# kill-switches_schematic.net
KiCad netlist of a schematic drawn in Altium Designer
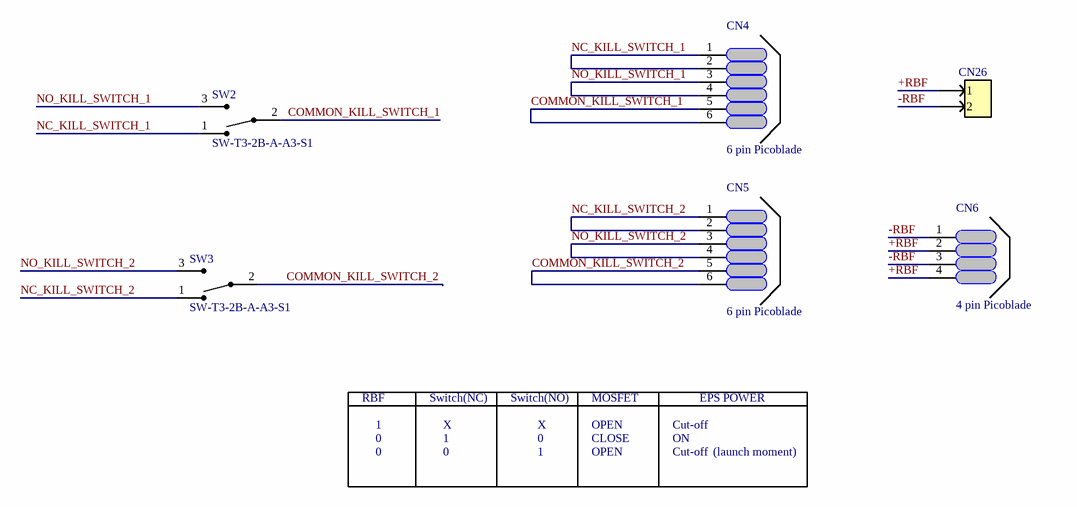
[diagram p0: kill-switches_schematic.SchDoc]

(export (version "E")
  (design (tool "Eeschema 10.0.6"))
  (components
    (comp (ref "CN4")
      (value "6 pin Picoblade")
      (footprint "PICO BLADE 0532610671")
      (description "1.25mm Pitch PicoBlade™ Header, Surface Mount, Vertical, 6 Circuits")
      (fields (field (name "MANUFACTURER") "Molex") (field (name "MANUFACTURER PART NUMBER") "53398-0671"))
      (libsource (lib "flatsat_platform_2") (part "53398-0671"))
    )
    (comp (ref "CN5")
      (value "6 pin Picoblade")
      (footprint "PICO BLADE 0532610671")
      (description "1.25mm Pitch PicoBlade™ Header, Surface Mount, Vertical, 6 Circuits")
      (fields (field (name "MANUFACTURER") "Molex") (field (name "MANUFACTURER PART NUMBER") "53398-0671"))
      (libsource (lib "flatsat_platform_2") (part "53398-0671"))
    )
    (comp (ref "CN6")
      (value "4 pin Picoblade")
      (footprint "PICO BLADE 0532610471")
      (description "1.25mm Pitch PicoBlade™ Header, Surface Mount, Vertical, 4 Circuits")
      (fields (field (name "MANUFACTURER") "Molex") (field (name "MANUFACTURER PART NUMBER") "53398-0471"))
      (libsource (lib "flatsat_platform_2") (part "0533980471"))
    )
    (comp (ref "CN26")
      (value "JST 2 position header 2.5mm")
      (footprint "B2B-XH-A-M(LF)(SN)")
      (description "CONN HEADER TOP 2POS 2.5MM GRN")
      (fields
        (field (name "MANUFACTURER") "JST")
        (field (name "MANUFACTURER PART NUMBER") "B2B-XH-A-M(LF)(SN)")
      )
      (libsource (lib "flatsat_platform_2") (part "B2B-XH-A-M(LF)(SN)"))
    )
    (comp (ref "SW2")
      (value "SW-T3-2B-A-A3-S1")
      (footprint "SW-T3-2B-A-A3-S1")
      (libsource (lib "SW-T3-2B-A-A3-S1") (part "SW-T3-2B-A-A3-S1"))
    )
    (comp (ref "SW3")
      (value "SW-T3-2B-A-A3-S1")
      (footprint "SW-T3-2B-A-A3-S1")
      (libsource (lib "SW-T3-2B-A-A3-S1") (part "SW-T3-2B-A-A3-S1"))
    )
  )
  (nets
    (net (code "1") (name "/+RBF") (class "Default")
      (node (ref "CN26") (pin "1") (pinfunction "1_1") (pintype "passive"))
      (node (ref "CN6") (pin "2") (pinfunction "2_2") (pintype "passive"))
      (node (ref "CN6") (pin "4") (pinfunction "4_4") (pintype "passive"))
    )
    (net (code "2") (name "/-RBF") (class "Default")
      (node (ref "CN26") (pin "2") (pinfunction "2_2") (pintype "passive"))
      (node (ref "CN6") (pin "1") (pinfunction "1_1") (pintype "passive"))
      (node (ref "CN6") (pin "3") (pinfunction "3_3") (pintype "passive"))
    )
    (net (code "3") (name "/COMMON_KILL_SWITCH_1") (class "Default")
      (node (ref "CN4") (pin "5") (pinfunction "5_5") (pintype "passive"))
      (node (ref "CN4") (pin "6") (pinfunction "6_6") (pintype "passive"))
      (node (ref "SW2") (pin "2") (pinfunction "COM_2") (pintype "passive"))
    )
    (net (code "4") (name "/COMMON_KILL_SWITCH_2") (class "Default")
      (node (ref "CN5") (pin "5") (pinfunction "5_5") (pintype "passive"))
      (node (ref "CN5") (pin "6") (pinfunction "6_6") (pintype "passive"))
      (node (ref "SW3") (pin "2") (pinfunction "COM_2") (pintype "passive"))
    )
    (net (code "5") (name "/NC_KILL_SWITCH_1") (class "Default")
      (node (ref "CN4") (pin "1") (pinfunction "1_1") (pintype "passive"))
      (node (ref "CN4") (pin "2") (pinfunction "2_2") (pintype "passive"))
      (node (ref "SW2") (pin "1") (pintype "passive"))
    )
    (net (code "6") (name "/NC_KILL_SWITCH_2") (class "Default")
      (node (ref "CN5") (pin "1") (pinfunction "1_1") (pintype "passive"))
      (node (ref "CN5") (pin "2") (pinfunction "2_2") (pintype "passive"))
      (node (ref "SW3") (pin "1") (pintype "passive"))
    )
    (net (code "7") (name "/NO_KILL_SWITCH_1") (class "Default")
      (node (ref "CN4") (pin "3") (pinfunction "3_3") (pintype "passive"))
      (node (ref "CN4") (pin "4") (pinfunction "4_4") (pintype "passive"))
      (node (ref "SW2") (pin "3") (pintype "passive"))
    )
    (net (code "8") (name "/NO_KILL_SWITCH_2") (class "Default")
      (node (ref "CN5") (pin "3") (pinfunction "3_3") (pintype "passive"))
      (node (ref "CN5") (pin "4") (pinfunction "4_4") (pintype "passive"))
      (node (ref "SW3") (pin "3") (pintype "passive"))
    )
  )
)
